# bitcoinChart.net
KiCad netlist of a schematic drawn in EAGLE
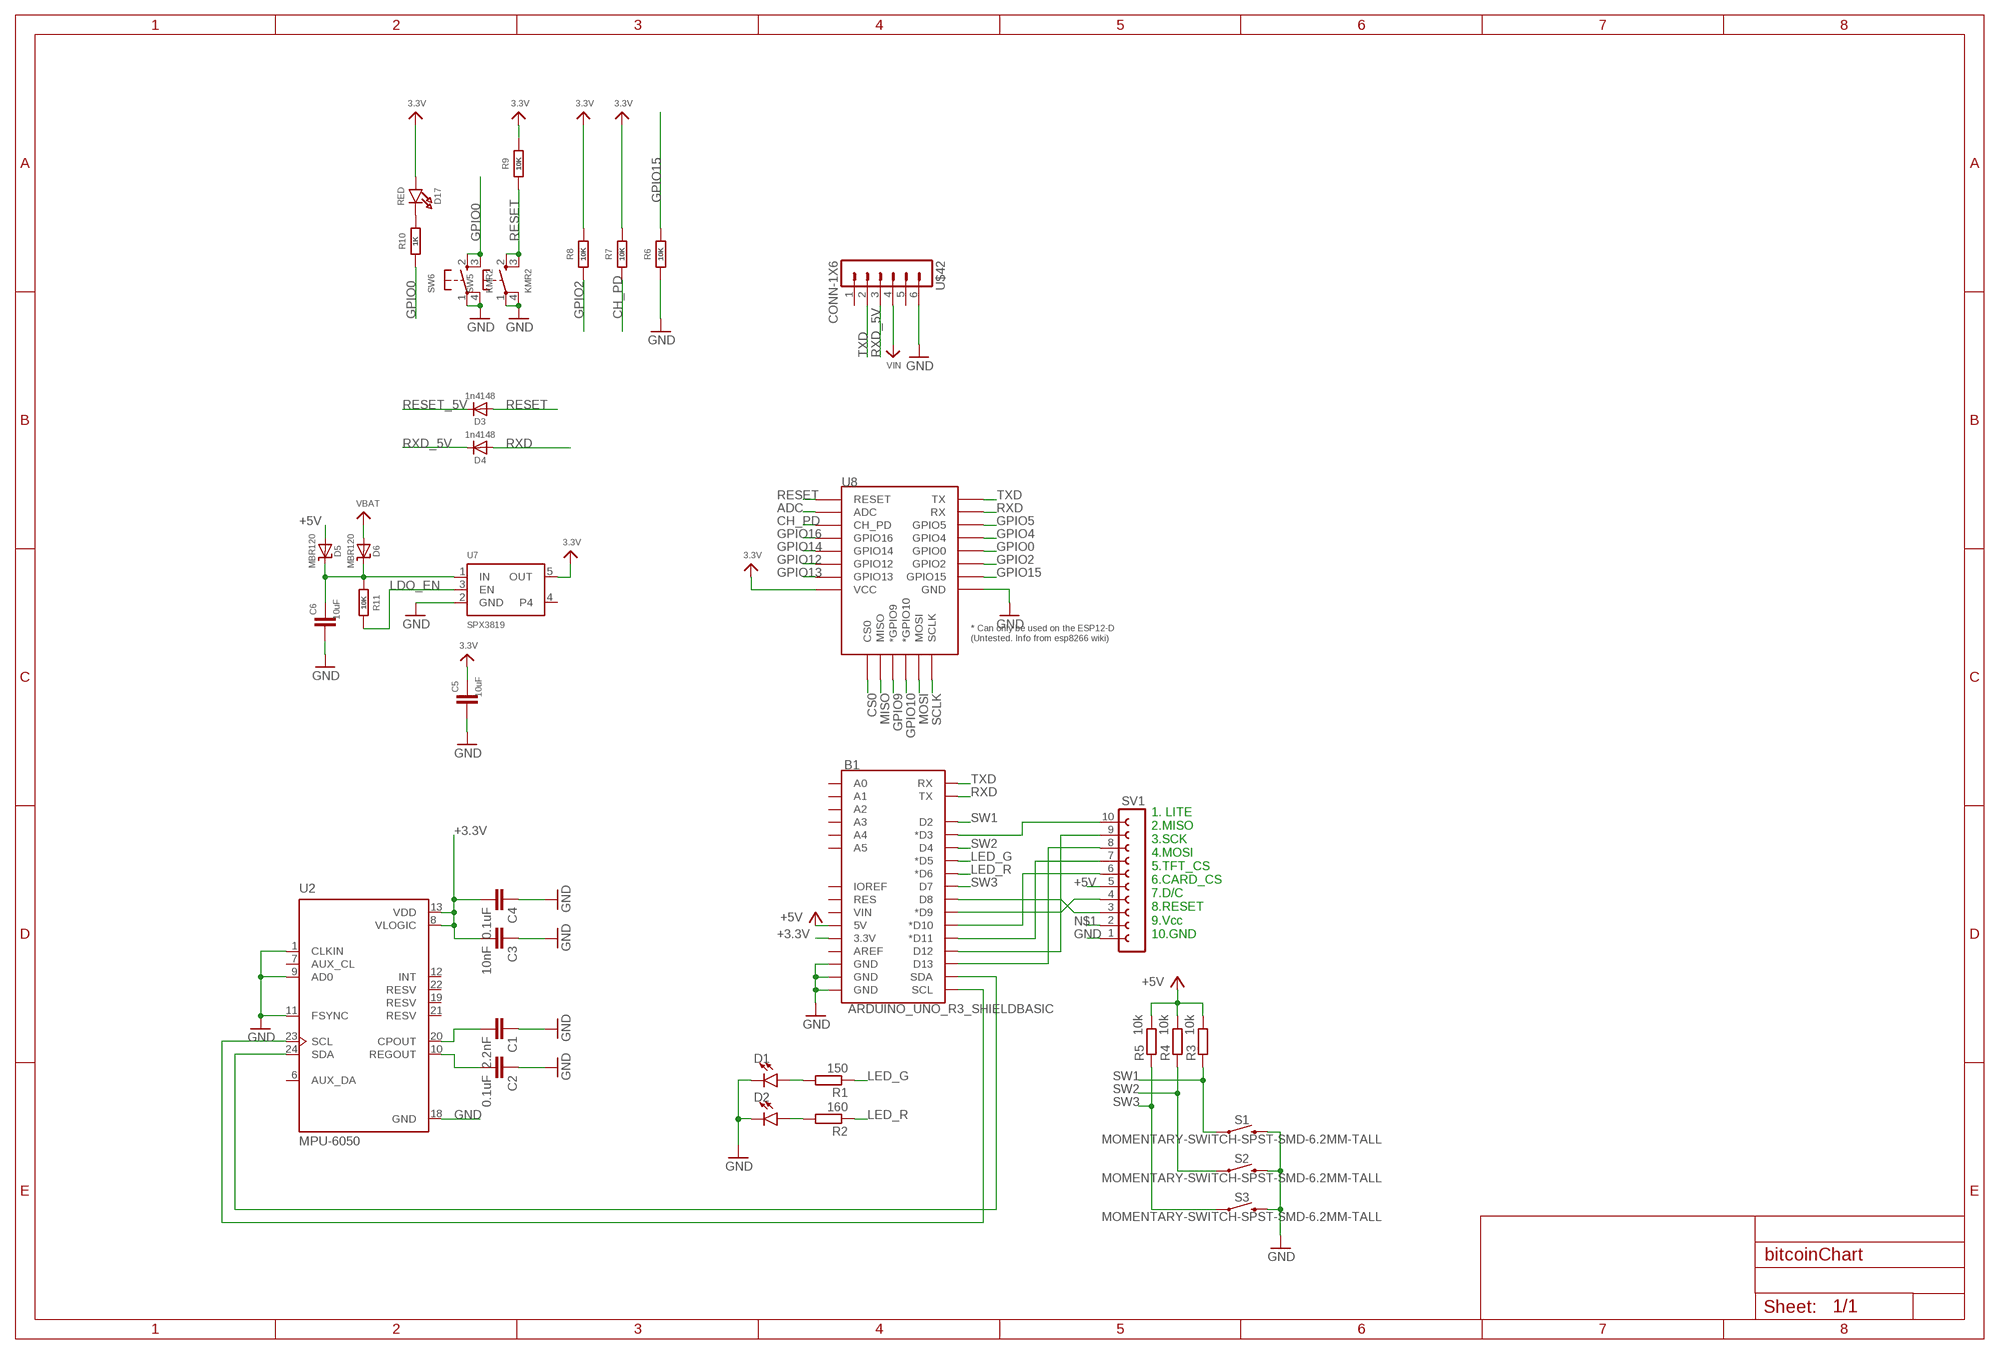
[diagram p0: schematic, sheet 1]

(export (version "E")
  (design (tool "Eeschema 10.0.6"))
  (components
    (comp (ref "B1")
      (value "ARDUINO_UNO_R3_SHIELDBASIC")
      (footprint "eagle-import:UNO_R3_SHIELD")
      (libsource (lib "eagle-import") (part "ARDUINO_UNO_R3_SHIELDBASIC"))
    )
    (comp (ref "C1")
      (value "2.2nF")
      (footprint "eagle-import:C1206K")
      (libsource (lib "eagle-import") (part "C-EUC1206K"))
    )
    (comp (ref "C2")
      (value "0.1uF")
      (footprint "eagle-import:C1206K")
      (libsource (lib "eagle-import") (part "C-EUC1206K"))
    )
    (comp (ref "C3")
      (value "10nF")
      (footprint "eagle-import:C1206K")
      (libsource (lib "eagle-import") (part "C-EUC1206K"))
    )
    (comp (ref "C4")
      (value "0.1uF")
      (footprint "eagle-import:C1206K")
      (libsource (lib "eagle-import") (part "C-EUC1206K"))
    )
    (comp (ref "C5")
      (value "10uF")
      (footprint "eagle-import:C0805K")
      (libsource (lib "eagle-import") (part "SMD-CAPACITOR0805"))
    )
    (comp (ref "C6")
      (value "10uF")
      (footprint "eagle-import:C0805K")
      (libsource (lib "eagle-import") (part "SMD-CAPACITOR0805"))
    )
    (comp (ref "D1")
      (value "GREEN")
      (footprint "eagle-import:CHIPLED_0805")
      (libsource (lib "eagle-import") (part "LEDCHIPLED_0805"))
    )
    (comp (ref "D2")
      (value "RED")
      (footprint "eagle-import:CHIPLED_0805")
      (libsource (lib "eagle-import") (part "LEDCHIPLED_0805"))
    )
    (comp (ref "D3")
      (value "1n4148")
      (footprint "eagle-import:SOD-323")
      (libsource (lib "eagle-import") (part "DIODESOD-323"))
    )
    (comp (ref "D4")
      (value "1n4148")
      (footprint "eagle-import:SOD-323")
      (libsource (lib "eagle-import") (part "DIODESOD-323"))
    )
    (comp (ref "D5")
      (value "MBR120")
      (footprint "eagle-import:SOD-123")
      (libsource (lib "eagle-import") (part "DIODE-SCHOTTKYSOD-123"))
    )
    (comp (ref "D6")
      (value "MBR120")
      (footprint "eagle-import:SOD-123")
      (libsource (lib "eagle-import") (part "DIODE-SCHOTTKYSOD-123"))
    )
    (comp (ref "D17")
      (value "RED")
      (footprint "eagle-import:LED_0805")
      (libsource (lib "eagle-import") (part "LED"))
    )
    (comp (ref "R1")
      (value "150")
      (footprint "eagle-import:M1206")
      (libsource (lib "eagle-import") (part "R-EU_M1206"))
    )
    (comp (ref "R2")
      (value "160")
      (footprint "eagle-import:M1206")
      (libsource (lib "eagle-import") (part "R-EU_M1206"))
    )
    (comp (ref "R3")
      (value "10k")
      (footprint "eagle-import:M1206")
      (libsource (lib "eagle-import") (part "R-EU_M1206"))
    )
    (comp (ref "R4")
      (value "10k")
      (footprint "eagle-import:M1206")
      (libsource (lib "eagle-import") (part "R-EU_M1206"))
    )
    (comp (ref "R5")
      (value "10k")
      (footprint "eagle-import:M1206")
      (libsource (lib "eagle-import") (part "R-EU_M1206"))
    )
    (comp (ref "R6")
      (value "10K")
      (footprint "eagle-import:R0805")
      (libsource (lib "eagle-import") (part "SMD-RESISTORR0805"))
    )
    (comp (ref "R7")
      (value "10K")
      (footprint "eagle-import:R0805")
      (libsource (lib "eagle-import") (part "SMD-RESISTORR0805"))
    )
    (comp (ref "R8")
      (value "10K")
      (footprint "eagle-import:R0805")
      (libsource (lib "eagle-import") (part "SMD-RESISTORR0805"))
    )
    (comp (ref "R9")
      (value "10K")
      (footprint "eagle-import:R0805")
      (libsource (lib "eagle-import") (part "SMD-RESISTORR0805"))
    )
    (comp (ref "R10")
      (value "1K")
      (footprint "eagle-import:R0805")
      (libsource (lib "eagle-import") (part "SMD-RESISTORR0805"))
    )
    (comp (ref "R11")
      (value "10K")
      (footprint "eagle-import:R0805")
      (libsource (lib "eagle-import") (part "SMD-RESISTORR0805"))
    )
    (comp (ref "S1")
      (value "MOMENTARY-SWITCH-SPST-SMD-6.2MM-TALL")
      (footprint "eagle-import:TACTILE_SWITCH_SMD_6.2MM_TALL")
      (libsource (lib "eagle-import") (part "MOMENTARY-SWITCH-SPST-SMD-6.2MM-TALL"))
    )
    (comp (ref "S2")
      (value "MOMENTARY-SWITCH-SPST-SMD-6.2MM-TALL")
      (footprint "eagle-import:TACTILE_SWITCH_SMD_6.2MM_TALL")
      (libsource (lib "eagle-import") (part "MOMENTARY-SWITCH-SPST-SMD-6.2MM-TALL"))
    )
    (comp (ref "S3")
      (value "MOMENTARY-SWITCH-SPST-SMD-6.2MM-TALL")
      (footprint "eagle-import:TACTILE_SWITCH_SMD_6.2MM_TALL")
      (libsource (lib "eagle-import") (part "MOMENTARY-SWITCH-SPST-SMD-6.2MM-TALL"))
    )
    (comp (ref "SV1")
      (value "FE10-1")
      (footprint "eagle-import:FE10")
      (libsource (lib "eagle-import") (part "FE10-1"))
    )
    (comp (ref "SW5")
      (value "KMR2")
      (footprint "eagle-import:BTN_KMR2")
      (libsource (lib "eagle-import") (part "BUTTON_KMR2KMR2"))
    )
    (comp (ref "SW6")
      (value "KMR2")
      (footprint "eagle-import:BTN_KMR2")
      (libsource (lib "eagle-import") (part "BUTTON_KMR2KMR2"))
    )
    (comp (ref "U$42")
      (value "CONN-1X6")
      (footprint "eagle-import:GHI-HEADERS_TH-1X6")
      (libsource (lib "eagle-import") (part "CONN-1X6"))
    )
    (comp (ref "U2")
      (value "MPU-6050")
      (footprint "eagle-import:QFN50P400X400X95-24N")
      (fields (field (name "MF") "TDK InvenSense"))
      (libsource (lib "eagle-import") (part "MPU-6050"))
    )
    (comp (ref "U7")
      (value "SPX3819")
      (footprint "eagle-import:SOT-23-5")
      (libsource (lib "eagle-import") (part "MIC5219SOT-23-5"))
    )
    (comp (ref "U8")
      (value "ESP12ESMD")
      (footprint "eagle-import:ESP12E-SMD")
      (libsource (lib "eagle-import") (part "ESP12ESMD"))
    )
  )
  (nets
    (net (code "1") (name "+5V") (class "Default")
      (node (ref "B1") (pin "5V") (pinfunction "5V_5V") (pintype "bidirectional"))
      (node (ref "D5") (pin "2") (pinfunction "A_2") (pintype "passive"))
      (node (ref "R3") (pin "2") (pinfunction "2_2") (pintype "passive"))
      (node (ref "R4") (pin "2") (pinfunction "2_2") (pintype "passive"))
      (node (ref "R5") (pin "2") (pinfunction "2_2") (pintype "passive"))
      (node (ref "SV1") (pin "5") (pinfunction "5_5") (pintype "passive"))
    )
    (net (code "2") (name "/+3.3V") (class "Default")
      (node (ref "B1") (pin "3.3V") (pinfunction "3.3V_3.3V") (pintype "bidirectional"))
      (node (ref "C3") (pin "2") (pinfunction "2_2") (pintype "passive"))
      (node (ref "C4") (pin "2") (pinfunction "2_2") (pintype "passive"))
      (node (ref "U2") (pin "13") (pinfunction "VDD_13") (pintype "power_in"))
      (node (ref "U2") (pin "8") (pinfunction "VLOGIC_8") (pintype "power_in"))
    )
    (net (code "3") (name "/ADC") (class "Default")
      (node (ref "U8") (pin "ADC") (pinfunction "ADC_ADC") (pintype "bidirectional"))
    )
    (net (code "4") (name "/CH_PD") (class "Default")
      (node (ref "R7") (pin "1") (pinfunction "1_1") (pintype "passive"))
      (node (ref "U8") (pin "CH_PD") (pinfunction "CH_PD_CH_PD") (pintype "bidirectional"))
    )
    (net (code "5") (name "/CS0") (class "Default")
      (node (ref "U8") (pin "CS0") (pinfunction "CS0_CS0") (pintype "bidirectional"))
    )
    (net (code "6") (name "/GPIO0") (class "Default")
      (node (ref "R10") (pin "1") (pinfunction "1_1") (pintype "passive"))
      (node (ref "SW6") (pin "2") (pinfunction "S_2") (pintype "passive"))
      (node (ref "SW6") (pin "3") (pinfunction "S1_3") (pintype "passive"))
      (node (ref "U8") (pin "GPIO0") (pinfunction "GPIO0_GPIO0") (pintype "bidirectional"))
    )
    (net (code "7") (name "/GPIO2") (class "Default")
      (node (ref "R8") (pin "1") (pinfunction "1_1") (pintype "passive"))
      (node (ref "U8") (pin "GPIO2") (pinfunction "GPIO2_GPIO2") (pintype "bidirectional"))
    )
    (net (code "8") (name "/GPIO4") (class "Default")
      (node (ref "U8") (pin "GPIO4") (pinfunction "GPIO4_GPIO4") (pintype "bidirectional"))
    )
    (net (code "9") (name "/GPIO5") (class "Default")
      (node (ref "U8") (pin "GPIO5") (pinfunction "GPIO5_GPIO5") (pintype "bidirectional"))
    )
    (net (code "10") (name "/GPIO9") (class "Default")
      (node (ref "U8") (pin "GPIO9") (pinfunction "*GPIO9_GPIO9") (pintype "bidirectional"))
    )
    (net (code "11") (name "/GPIO10") (class "Default")
      (node (ref "U8") (pin "GPIO10") (pinfunction "*GPIO10_GPIO10") (pintype "bidirectional"))
    )
    (net (code "12") (name "/GPIO12") (class "Default")
      (node (ref "U8") (pin "GPIO12") (pinfunction "GPIO12_GPIO12") (pintype "bidirectional"))
    )
    (net (code "13") (name "/GPIO13") (class "Default")
      (node (ref "U8") (pin "GPIO13") (pinfunction "GPIO13_GPIO13") (pintype "bidirectional"))
    )
    (net (code "14") (name "/GPIO14") (class "Default")
      (node (ref "U8") (pin "GPIO14") (pinfunction "GPIO14_GPIO14") (pintype "bidirectional"))
    )
    (net (code "15") (name "/GPIO15") (class "Default")
      (node (ref "R6") (pin "2") (pinfunction "2_2") (pintype "passive"))
      (node (ref "U8") (pin "GPIO15") (pinfunction "GPIO15_GPIO15") (pintype "bidirectional"))
    )
    (net (code "16") (name "/GPIO16") (class "Default")
      (node (ref "U8") (pin "GPIO16") (pinfunction "GPIO16_GPIO16") (pintype "bidirectional"))
    )
    (net (code "17") (name "/LDO_EN") (class "Default")
      (node (ref "R11") (pin "2") (pinfunction "2_2") (pintype "passive"))
      (node (ref "U7") (pin "3") (pinfunction "EN_3") (pintype "bidirectional"))
    )
    (net (code "18") (name "/LED_G") (class "Default")
      (node (ref "B1") (pin "D5") (pinfunction "*D5_D5") (pintype "bidirectional"))
      (node (ref "R1") (pin "1") (pinfunction "1_1") (pintype "passive"))
    )
    (net (code "19") (name "/LED_R") (class "Default")
      (node (ref "B1") (pin "D6") (pinfunction "*D6_D6") (pintype "bidirectional"))
      (node (ref "R2") (pin "1") (pinfunction "1_1") (pintype "passive"))
    )
    (net (code "20") (name "/MISO") (class "Default")
      (node (ref "U8") (pin "MISO") (pinfunction "MISO_MISO") (pintype "bidirectional"))
    )
    (net (code "21") (name "/MOSI") (class "Default")
      (node (ref "U8") (pin "MOSI") (pinfunction "MOSI_MOSI") (pintype "bidirectional"))
    )
    (net (code "22") (name "/N$1") (class "Default")
      (node (ref "SV1") (pin "2") (pinfunction "2_2") (pintype "passive"))
    )
    (net (code "23") (name "/RESET") (class "Default")
      (node (ref "D3") (pin "2") (pinfunction "A_2") (pintype "passive"))
      (node (ref "R9") (pin "1") (pinfunction "1_1") (pintype "passive"))
      (node (ref "SW5") (pin "2") (pinfunction "S_2") (pintype "passive"))
      (node (ref "SW5") (pin "3") (pinfunction "S1_3") (pintype "passive"))
      (node (ref "U8") (pin "RESET") (pinfunction "RESET_RESET") (pintype "bidirectional"))
    )
    (net (code "24") (name "/RESET_5V") (class "Default")
      (node (ref "D3") (pin "1") (pinfunction "C_1") (pintype "passive"))
    )
    (net (code "25") (name "/RXD") (class "Default")
      (node (ref "B1") (pin "TX") (pinfunction "TX_TX") (pintype "bidirectional"))
      (node (ref "D4") (pin "2") (pinfunction "A_2") (pintype "passive"))
      (node (ref "U8") (pin "RXD0") (pinfunction "RX_RXD0") (pintype "bidirectional"))
    )
    (net (code "26") (name "/RXD_5V") (class "Default")
      (node (ref "D4") (pin "1") (pinfunction "C_1") (pintype "passive"))
      (node (ref "U$42") (pin "3") (pinfunction "3_3") (pintype "passive"))
    )
    (net (code "27") (name "/SCLK") (class "Default")
      (node (ref "U8") (pin "SCLK") (pinfunction "SCLK_SCLK") (pintype "bidirectional"))
    )
    (net (code "28") (name "/SW1") (class "Default")
      (node (ref "B1") (pin "D2") (pinfunction "D2_D2") (pintype "bidirectional"))
      (node (ref "R3") (pin "1") (pinfunction "1_1") (pintype "passive"))
      (node (ref "S1") (pin "A2") (pinfunction "1_A2") (pintype "passive"))
    )
    (net (code "29") (name "/SW2") (class "Default")
      (node (ref "B1") (pin "D4") (pinfunction "D4_D4") (pintype "bidirectional"))
      (node (ref "R4") (pin "1") (pinfunction "1_1") (pintype "passive"))
      (node (ref "S2") (pin "A2") (pinfunction "1_A2") (pintype "passive"))
    )
    (net (code "30") (name "/SW3") (class "Default")
      (node (ref "B1") (pin "D7") (pinfunction "D7_D7") (pintype "bidirectional"))
      (node (ref "R5") (pin "1") (pinfunction "1_1") (pintype "passive"))
      (node (ref "S3") (pin "A2") (pinfunction "1_A2") (pintype "passive"))
    )
    (net (code "31") (name "/TXD") (class "Default")
      (node (ref "B1") (pin "RX") (pinfunction "RX_RX") (pintype "bidirectional"))
      (node (ref "U$42") (pin "2") (pinfunction "2_2") (pintype "passive"))
      (node (ref "U8") (pin "TXD0") (pinfunction "TX_TXD0") (pintype "bidirectional"))
    )
    (net (code "32") (name "3.3V") (class "Default")
      (node (ref "C5") (pin "1") (pinfunction "1_1") (pintype "passive"))
      (node (ref "D17") (pin "A") (pinfunction "A_A") (pintype "passive"))
      (node (ref "R7") (pin "2") (pinfunction "2_2") (pintype "passive"))
      (node (ref "R8") (pin "2") (pinfunction "2_2") (pintype "passive"))
      (node (ref "R9") (pin "2") (pinfunction "2_2") (pintype "passive"))
      (node (ref "U7") (pin "5") (pinfunction "OUT_5") (pintype "bidirectional"))
      (node (ref "U8") (pin "VCC") (pinfunction "VCC_VCC") (pintype "bidirectional"))
    )
    (net (code "33") (name "GND") (class "Default")
      (node (ref "B1") (pin "GND@0") (pinfunction "GND_GND@0") (pintype "bidirectional"))
      (node (ref "B1") (pin "GND@1") (pinfunction "GND_GND@1") (pintype "bidirectional"))
      (node (ref "B1") (pin "GND@2") (pinfunction "GND_GND@2") (pintype "bidirectional"))
      (node (ref "C1") (pin "1") (pinfunction "1_1") (pintype "passive"))
      (node (ref "C2") (pin "1") (pinfunction "1_1") (pintype "passive"))
      (node (ref "C3") (pin "1") (pinfunction "1_1") (pintype "passive"))
      (node (ref "C4") (pin "1") (pinfunction "1_1") (pintype "passive"))
      (node (ref "C5") (pin "2") (pinfunction "2_2") (pintype "passive"))
      (node (ref "C6") (pin "2") (pinfunction "2_2") (pintype "passive"))
      (node (ref "D1") (pin "C") (pinfunction "C_C") (pintype "passive"))
      (node (ref "D2") (pin "C") (pinfunction "C_C") (pintype "passive"))
      (node (ref "R6") (pin "1") (pinfunction "1_1") (pintype "passive"))
      (node (ref "S1") (pin "B2") (pinfunction "2_B2") (pintype "passive"))
      (node (ref "S2") (pin "B2") (pinfunction "2_B2") (pintype "passive"))
      (node (ref "S3") (pin "B2") (pinfunction "2_B2") (pintype "passive"))
      (node (ref "SV1") (pin "1") (pinfunction "1_1") (pintype "passive"))
      (node (ref "SW5") (pin "1") (pinfunction "P_1") (pintype "passive"))
      (node (ref "SW5") (pin "4") (pinfunction "P1_4") (pintype "passive"))
      (node (ref "SW6") (pin "1") (pinfunction "P_1") (pintype "passive"))
      (node (ref "SW6") (pin "4") (pinfunction "P1_4") (pintype "passive"))
      (node (ref "U$42") (pin "6") (pinfunction "6_6") (pintype "passive"))
      (node (ref "U2") (pin "1") (pinfunction "CLKIN_1") (pintype "input"))
      (node (ref "U2") (pin "11") (pinfunction "FSYNC_11") (pintype "input"))
      (node (ref "U2") (pin "18") (pinfunction "GND_18") (pintype "power_in"))
      (node (ref "U2") (pin "9") (pinfunction "AD0_9") (pintype "input"))
      (node (ref "U7") (pin "2") (pinfunction "GND_2") (pintype "bidirectional"))
      (node (ref "U8") (pin "GND") (pinfunction "GND_GND") (pintype "bidirectional"))
    )
    (net (code "34") (name "Net-(B1-*D3)") (class "Default")
      (node (ref "B1") (pin "D3") (pinfunction "*D3_D3") (pintype "bidirectional"))
      (node (ref "SV1") (pin "10") (pinfunction "10_10") (pintype "passive"))
    )
    (net (code "35") (name "Net-(B1-*D9)") (class "Default")
      (node (ref "B1") (pin "D9") (pinfunction "*D9_D9") (pintype "bidirectional"))
      (node (ref "SV1") (pin "4") (pinfunction "4_4") (pintype "passive"))
    )
    (net (code "36") (name "Net-(B1-*D10)") (class "Default")
      (node (ref "B1") (pin "D10") (pinfunction "*D10_D10") (pintype "bidirectional"))
      (node (ref "SV1") (pin "6") (pinfunction "6_6") (pintype "passive"))
    )
    (net (code "37") (name "Net-(B1-*D11)") (class "Default")
      (node (ref "B1") (pin "D11") (pinfunction "*D11_D11") (pintype "bidirectional"))
      (node (ref "SV1") (pin "7") (pinfunction "7_7") (pintype "passive"))
    )
    (net (code "38") (name "Net-(B1-PadD8)") (class "Default")
      (node (ref "B1") (pin "D8") (pinfunction "D8_D8") (pintype "bidirectional"))
      (node (ref "SV1") (pin "3") (pinfunction "3_3") (pintype "passive"))
    )
    (net (code "39") (name "Net-(B1-PadD12)") (class "Default")
      (node (ref "B1") (pin "D12") (pinfunction "D12_D12") (pintype "bidirectional"))
      (node (ref "SV1") (pin "9") (pinfunction "9_9") (pintype "passive"))
    )
    (net (code "40") (name "Net-(B1-PadD13)") (class "Default")
      (node (ref "B1") (pin "D13") (pinfunction "D13_D13") (pintype "bidirectional"))
      (node (ref "SV1") (pin "8") (pinfunction "8_8") (pintype "passive"))
    )
    (net (code "41") (name "Net-(D1-PadA)") (class "Default")
      (node (ref "D1") (pin "A") (pinfunction "A_A") (pintype "passive"))
      (node (ref "R1") (pin "2") (pinfunction "2_2") (pintype "passive"))
    )
    (net (code "42") (name "Net-(D2-PadA)") (class "Default")
      (node (ref "D2") (pin "A") (pinfunction "A_A") (pintype "passive"))
      (node (ref "R2") (pin "2") (pinfunction "2_2") (pintype "passive"))
    )
    (net (code "43") (name "Net-(D5-C)") (class "Default")
      (node (ref "C6") (pin "1") (pinfunction "1_1") (pintype "passive"))
      (node (ref "D5") (pin "1") (pinfunction "C_1") (pintype "passive"))
      (node (ref "D6") (pin "1") (pinfunction "C_1") (pintype "passive"))
      (node (ref "R11") (pin "1") (pinfunction "1_1") (pintype "passive"))
      (node (ref "U7") (pin "1") (pinfunction "IN_1") (pintype "bidirectional"))
    )
    (net (code "44") (name "Net-(D17-C)") (class "Default")
      (node (ref "D17") (pin "K") (pinfunction "C_K") (pintype "passive"))
      (node (ref "R10") (pin "2") (pinfunction "2_2") (pintype "passive"))
    )
    (net (code "45") (name "Net-(U2-CPOUT)") (class "Default")
      (node (ref "C1") (pin "2") (pinfunction "2_2") (pintype "passive"))
      (node (ref "U2") (pin "20") (pinfunction "CPOUT_20") (pintype "passive"))
    )
    (net (code "46") (name "Net-(U2-REGOUT)") (class "Default")
      (node (ref "C2") (pin "2") (pinfunction "2_2") (pintype "passive"))
      (node (ref "U2") (pin "10") (pinfunction "REGOUT_10") (pintype "passive"))
    )
    (net (code "47") (name "Net-(U2-SCL)") (class "Default")
      (node (ref "B1") (pin "SCL") (pinfunction "SCL_SCL") (pintype "bidirectional"))
      (node (ref "U2") (pin "23") (pinfunction "SCL_23") (pintype "input"))
    )
    (net (code "48") (name "Net-(U2-SDA)") (class "Default")
      (node (ref "B1") (pin "SDA") (pinfunction "SDA_SDA") (pintype "bidirectional"))
      (node (ref "U2") (pin "24") (pinfunction "SDA_24") (pintype "bidirectional"))
    )
    (net (code "49") (name "VBAT") (class "Default")
      (node (ref "D6") (pin "2") (pinfunction "A_2") (pintype "passive"))
    )
    (net (code "50") (name "VIN") (class "Default")
      (node (ref "U$42") (pin "4") (pinfunction "4_4") (pintype "passive"))
    )
    (net (code "51") (name "unconnected-(B1-PadA0)") (class "Default")
      (node (ref "B1") (pin "A0") (pinfunction "A0_A0") (pintype "bidirectional"))
    )
    (net (code "52") (name "unconnected-(B1-PadA1)") (class "Default")
      (node (ref "B1") (pin "A1") (pinfunction "A1_A1") (pintype "bidirectional"))
    )
    (net (code "53") (name "unconnected-(B1-PadA2)") (class "Default")
      (node (ref "B1") (pin "A2") (pinfunction "A2_A2") (pintype "bidirectional"))
    )
    (net (code "54") (name "unconnected-(B1-PadA3)") (class "Default")
      (node (ref "B1") (pin "A3") (pinfunction "A3_A3") (pintype "bidirectional"))
    )
    (net (code "55") (name "unconnected-(B1-PadA4)") (class "Default")
      (node (ref "B1") (pin "A4") (pinfunction "A4_A4") (pintype "bidirectional"))
    )
    (net (code "56") (name "unconnected-(B1-PadA5)") (class "Default")
      (node (ref "B1") (pin "A5") (pinfunction "A5_A5") (pintype "bidirectional"))
    )
    (net (code "57") (name "unconnected-(B1-PadAREF)") (class "Default")
      (node (ref "B1") (pin "AREF") (pinfunction "AREF_AREF") (pintype "bidirectional"))
    )
    (net (code "58") (name "unconnected-(B1-PadIOREF)") (class "Default")
      (node (ref "B1") (pin "IOREF") (pinfunction "IOREF_IOREF") (pintype "bidirectional"))
    )
    (net (code "59") (name "unconnected-(B1-PadRES)") (class "Default")
      (node (ref "B1") (pin "RES") (pinfunction "RES_RES") (pintype "bidirectional"))
    )
    (net (code "60") (name "unconnected-(B1-PadVIN)") (class "Default")
      (node (ref "B1") (pin "VIN") (pinfunction "VIN_VIN") (pintype "bidirectional"))
    )
    (net (code "61") (name "unconnected-(U$42-Pad1)") (class "Default")
      (node (ref "U$42") (pin "1") (pinfunction "1_1") (pintype "passive"))
    )
    (net (code "62") (name "unconnected-(U$42-Pad5)") (class "Default")
      (node (ref "U$42") (pin "5") (pinfunction "5_5") (pintype "passive"))
    )
    (net (code "63") (name "unconnected-(U2-AUX_CL-Pad7)") (class "Default")
      (node (ref "U2") (pin "7") (pinfunction "AUX_CL_7") (pintype "input"))
    )
    (net (code "64") (name "unconnected-(U2-AUX_DA-Pad6)") (class "Default")
      (node (ref "U2") (pin "6") (pinfunction "AUX_DA_6") (pintype "bidirectional"))
    )
    (net (code "65") (name "unconnected-(U2-INT-Pad12)") (class "Default")
      (node (ref "U2") (pin "12") (pinfunction "INT_12") (pintype "output"))
    )
    (net (code "66") (name "unconnected-(U2-RESV-Pad19)") (class "Default")
      (node (ref "U2") (pin "19") (pinfunction "RESV_19") (pintype "passive"))
    )
    (net (code "67") (name "unconnected-(U2-RESV-Pad21)") (class "Default")
      (node (ref "U2") (pin "21") (pinfunction "RESV_21") (pintype "passive"))
    )
    (net (code "68") (name "unconnected-(U2-RESV-Pad22)") (class "Default")
      (node (ref "U2") (pin "22") (pinfunction "RESV_22") (pintype "passive"))
    )
    (net (code "69") (name "unconnected-(U7-P4-Pad4)") (class "Default")
      (node (ref "U7") (pin "4") (pinfunction "P4_4") (pintype "bidirectional"))
    )
  )
)
